# LIC_rack_OV-03.net
KiCad netlist of a schematic drawn in EAGLE
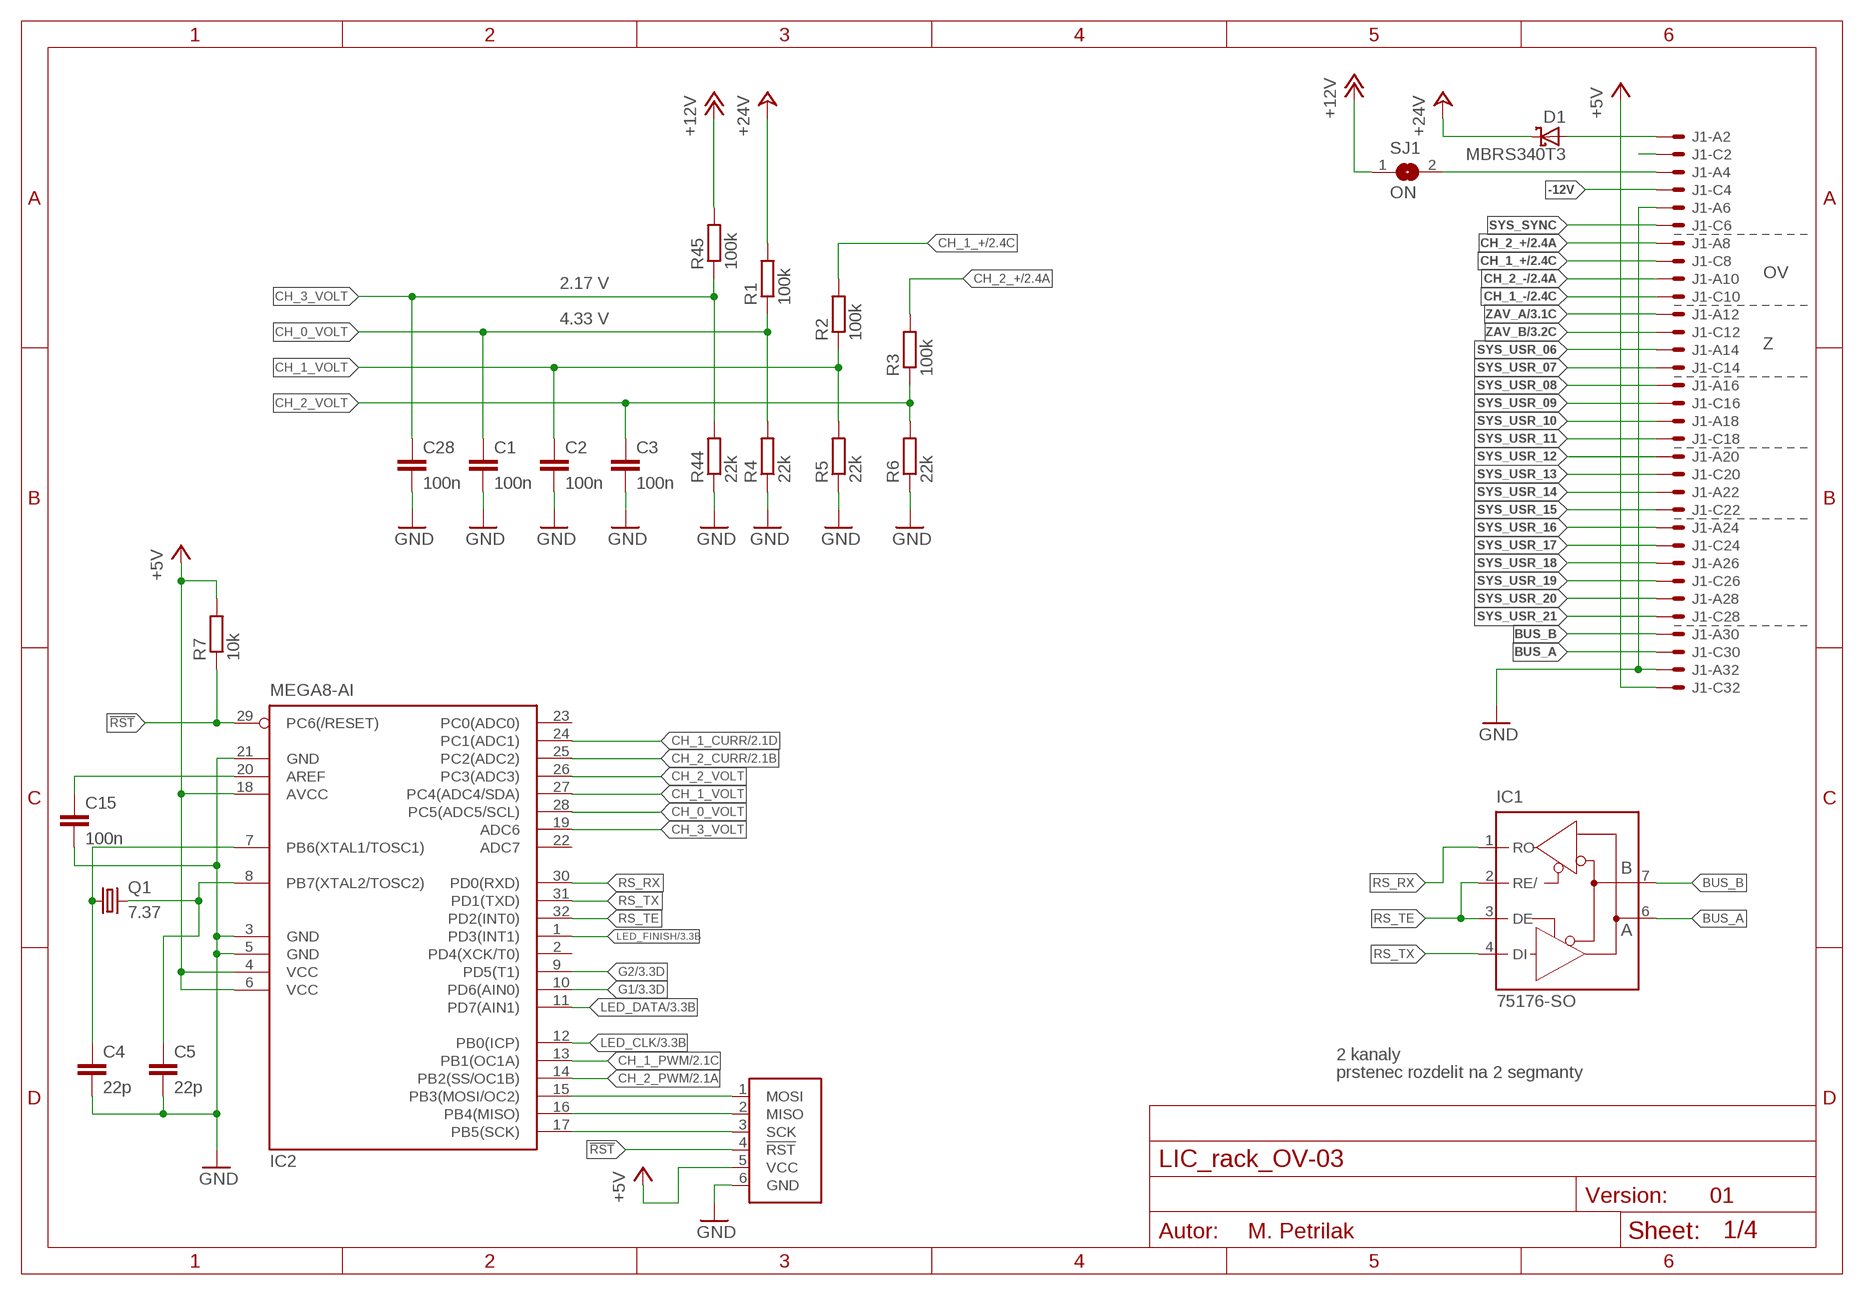
[diagram p0: schematic, sheet 1]
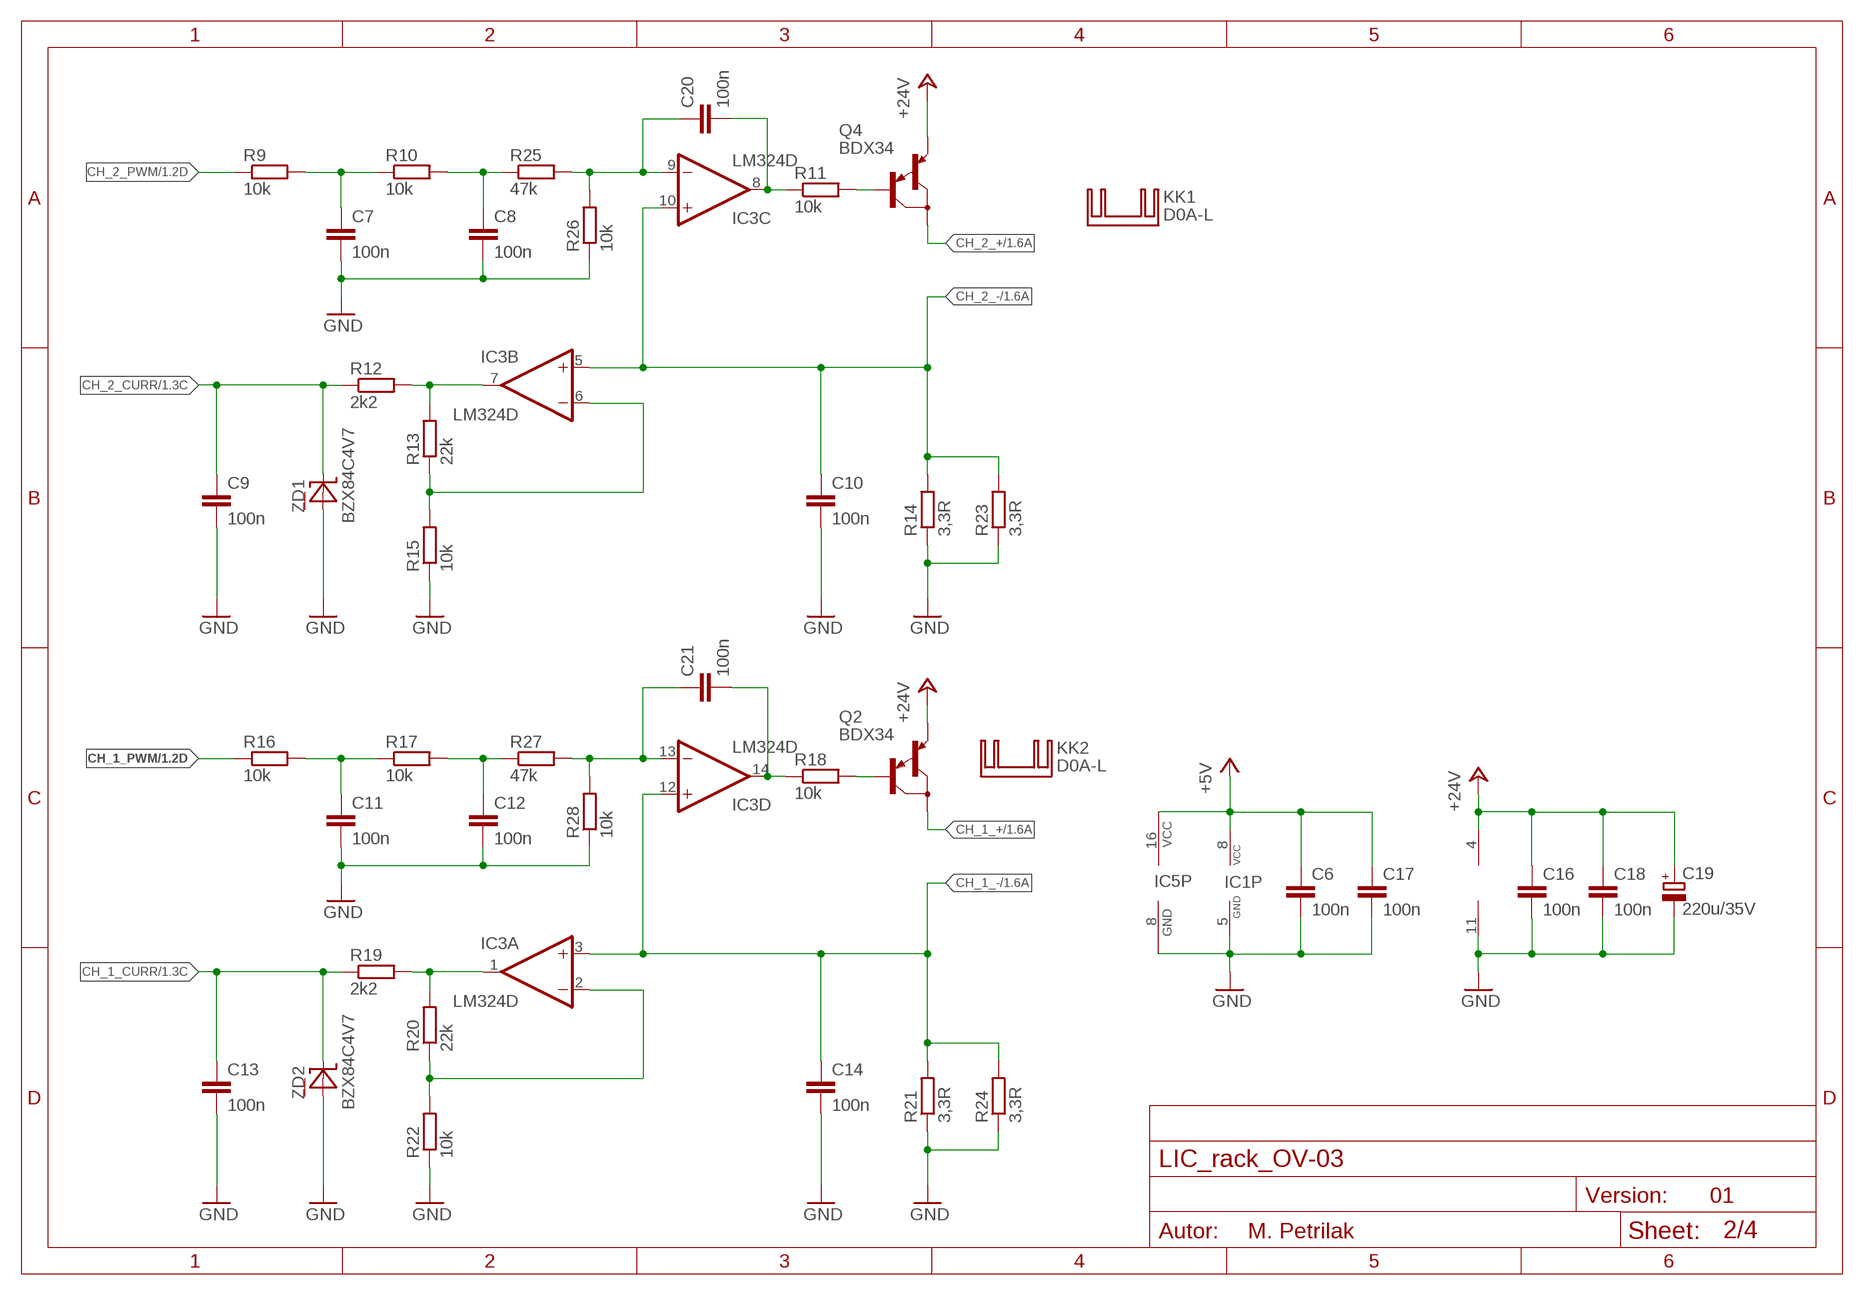
[diagram p1: schematic, sheet 2]
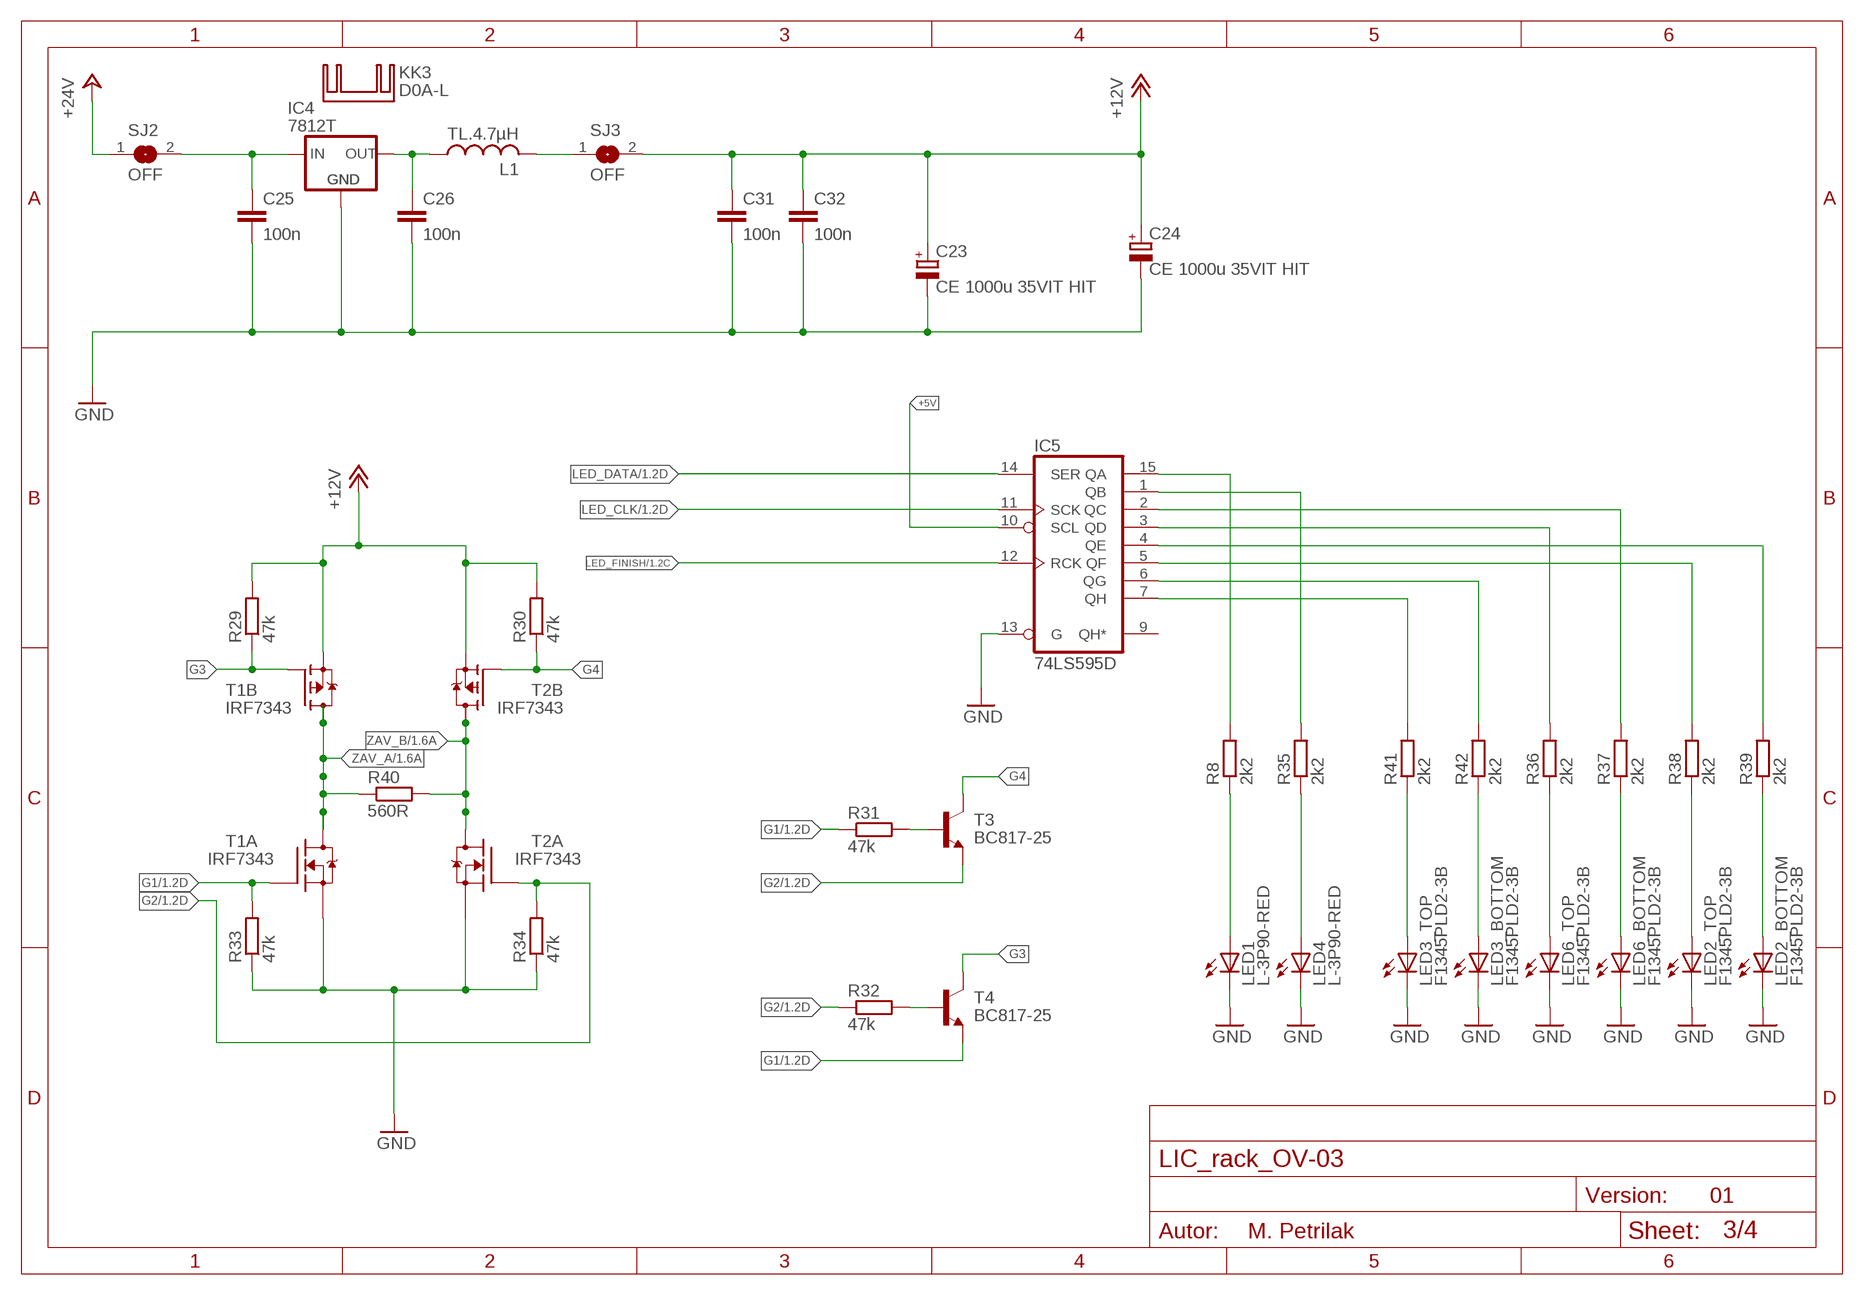
[diagram p2: schematic, sheet 3]

(export (version "E")
  (design (tool "Eeschema 10.0.6"))
  (components
    (comp (ref "C6")
      (value "100n")
      (footprint "eagle-import:C1206")
      (libsource (lib "eagle-import") (part "C-EUC1206"))
    )
    (comp (ref "C7")
      (value "100n")
      (footprint "eagle-import:C1206")
      (libsource (lib "eagle-import") (part "C-EUC1206"))
    )
    (comp (ref "C8")
      (value "100n")
      (footprint "eagle-import:C1206")
      (libsource (lib "eagle-import") (part "C-EUC1206"))
    )
    (comp (ref "C9")
      (value "100n")
      (footprint "eagle-import:C1206")
      (libsource (lib "eagle-import") (part "C-EUC1206"))
    )
    (comp (ref "C10")
      (value "100n")
      (footprint "eagle-import:C1206")
      (libsource (lib "eagle-import") (part "C-EUC1206"))
    )
    (comp (ref "C11")
      (value "100n")
      (footprint "eagle-import:C1206")
      (libsource (lib "eagle-import") (part "C-EUC1206"))
    )
    (comp (ref "C12")
      (value "100n")
      (footprint "eagle-import:C1206")
      (libsource (lib "eagle-import") (part "C-EUC1206"))
    )
    (comp (ref "C13")
      (value "100n")
      (footprint "eagle-import:C1206")
      (libsource (lib "eagle-import") (part "C-EUC1206"))
    )
    (comp (ref "C14")
      (value "100n")
      (footprint "eagle-import:C1206")
      (libsource (lib "eagle-import") (part "C-EUC1206"))
    )
    (comp (ref "C16")
      (value "100n")
      (footprint "eagle-import:C1206")
      (libsource (lib "eagle-import") (part "C-EUC1206"))
    )
    (comp (ref "C17")
      (value "100n")
      (footprint "eagle-import:C1206")
      (libsource (lib "eagle-import") (part "C-EUC1206"))
    )
    (comp (ref "C18")
      (value "100n")
      (footprint "eagle-import:C1206")
      (libsource (lib "eagle-import") (part "C-EUC1206"))
    )
    (comp (ref "C19")
      (value "220u/35V")
      (footprint "eagle-import:E3,5-8LR")
      (libsource (lib "eagle-import") (part "CPOL-EUE3.5-8LR"))
    )
    (comp (ref "C20")
      (value "100n")
      (footprint "eagle-import:C1206")
      (libsource (lib "eagle-import") (part "C-EUC1206"))
    )
    (comp (ref "C21")
      (value "100n")
      (footprint "eagle-import:C1206")
      (libsource (lib "eagle-import") (part "C-EUC1206"))
    )
    (comp (ref "IC1")
      (value "75176-SO")
      (footprint "eagle-import:SO08")
      (libsource (lib "eagle-import") (part "75176-SO"))
    )
    (comp (ref "IC3")
      (value "LM324D")
      (footprint "eagle-import:SO14")
      (libsource (lib "eagle-import") (part "LM324D"))
    )
    (comp (ref "IC5")
      (value "74LS595D")
      (footprint "eagle-import:SO16")
      (libsource (lib "eagle-import") (part "74595DLS"))
    )
    (comp (ref "KK1")
      (value "D0A-L")
      (footprint "eagle-import:D02A-L")
      (libsource (lib "eagle-import") (part "D0A-L"))
    )
    (comp (ref "KK2")
      (value "D0A-L")
      (footprint "eagle-import:D02A-L")
      (libsource (lib "eagle-import") (part "D0A-L"))
    )
    (comp (ref "Q2")
      (value "BDX34")
      (footprint "eagle-import:TO220")
      (libsource (lib "eagle-import") (part "BDX34"))
    )
    (comp (ref "Q4")
      (value "BDX34")
      (footprint "eagle-import:TO220")
      (libsource (lib "eagle-import") (part "BDX34"))
    )
    (comp (ref "R9")
      (value "10k")
      (footprint "eagle-import:R1206")
      (libsource (lib "eagle-import") (part "R-EU_R1206"))
    )
    (comp (ref "R10")
      (value "10k")
      (footprint "eagle-import:R1206")
      (libsource (lib "eagle-import") (part "R-EU_R1206"))
    )
    (comp (ref "R11")
      (value "10k")
      (footprint "eagle-import:R1206")
      (libsource (lib "eagle-import") (part "R-EU_R1206"))
    )
    (comp (ref "R12")
      (value "2k2")
      (footprint "eagle-import:R1206")
      (libsource (lib "eagle-import") (part "R-EU_R1206"))
    )
    (comp (ref "R13")
      (value "22k")
      (footprint "eagle-import:R1206")
      (libsource (lib "eagle-import") (part "R-EU_R1206"))
    )
    (comp (ref "R14")
      (value "3,3R")
      (footprint "eagle-import:0309_12")
      (libsource (lib "eagle-import") (part "R-EU_0309/12"))
    )
    (comp (ref "R15")
      (value "10k")
      (footprint "eagle-import:R1206")
      (libsource (lib "eagle-import") (part "R-EU_R1206"))
    )
    (comp (ref "R16")
      (value "10k")
      (footprint "eagle-import:R1206")
      (libsource (lib "eagle-import") (part "R-EU_R1206"))
    )
    (comp (ref "R17")
      (value "10k")
      (footprint "eagle-import:R1206")
      (libsource (lib "eagle-import") (part "R-EU_R1206"))
    )
    (comp (ref "R18")
      (value "10k")
      (footprint "eagle-import:R1206")
      (libsource (lib "eagle-import") (part "R-EU_R1206"))
    )
    (comp (ref "R19")
      (value "2k2")
      (footprint "eagle-import:R1206")
      (libsource (lib "eagle-import") (part "R-EU_R1206"))
    )
    (comp (ref "R20")
      (value "22k")
      (footprint "eagle-import:R1206")
      (libsource (lib "eagle-import") (part "R-EU_R1206"))
    )
    (comp (ref "R21")
      (value "3,3R")
      (footprint "eagle-import:0309_12")
      (libsource (lib "eagle-import") (part "R-EU_0309/12"))
    )
    (comp (ref "R22")
      (value "10k")
      (footprint "eagle-import:R1206")
      (libsource (lib "eagle-import") (part "R-EU_R1206"))
    )
    (comp (ref "R23")
      (value "3,3R")
      (footprint "eagle-import:R1206")
      (libsource (lib "eagle-import") (part "R-EU_R1206"))
    )
    (comp (ref "R24")
      (value "3,3R")
      (footprint "eagle-import:R1206")
      (libsource (lib "eagle-import") (part "R-EU_R1206"))
    )
    (comp (ref "R25")
      (value "47k")
      (footprint "eagle-import:R1206")
      (libsource (lib "eagle-import") (part "R-EU_R1206"))
    )
    (comp (ref "R26")
      (value "10k")
      (footprint "eagle-import:R1206")
      (libsource (lib "eagle-import") (part "R-EU_R1206"))
    )
    (comp (ref "R27")
      (value "47k")
      (footprint "eagle-import:R1206")
      (libsource (lib "eagle-import") (part "R-EU_R1206"))
    )
    (comp (ref "R28")
      (value "10k")
      (footprint "eagle-import:R1206")
      (libsource (lib "eagle-import") (part "R-EU_R1206"))
    )
    (comp (ref "ZD1")
      (value "BZX84C4V7")
      (footprint "eagle-import:SOT23")
      (libsource (lib "eagle-import") (part "BZX84C4V7"))
    )
    (comp (ref "ZD2")
      (value "BZX84C4V7")
      (footprint "eagle-import:SOT23")
      (libsource (lib "eagle-import") (part "BZX84C4V7"))
    )
    (comp (ref "C1")
      (value "100n")
      (footprint "eagle-import:C1206")
      (libsource (lib "eagle-import") (part "C-EUC1206"))
    )
    (comp (ref "C2")
      (value "100n")
      (footprint "eagle-import:C1206")
      (libsource (lib "eagle-import") (part "C-EUC1206"))
    )
    (comp (ref "C3")
      (value "100n")
      (footprint "eagle-import:C1206")
      (libsource (lib "eagle-import") (part "C-EUC1206"))
    )
    (comp (ref "C4")
      (value "22p")
      (footprint "eagle-import:C0805")
      (libsource (lib "eagle-import") (part "C-EUC0805"))
    )
    (comp (ref "C5")
      (value "22p")
      (footprint "eagle-import:C0805")
      (libsource (lib "eagle-import") (part "C-EUC0805"))
    )
    (comp (ref "C15")
      (value "100n")
      (footprint "eagle-import:C1206")
      (libsource (lib "eagle-import") (part "C-EUC1206"))
    )
    (comp (ref "C28")
      (value "100n")
      (footprint "eagle-import:C1206")
      (libsource (lib "eagle-import") (part "C-EUC1206"))
    )
    (comp (ref "D1")
      (value "MBRS340T3")
      (footprint "eagle-import:SMC")
      (libsource (lib "eagle-import") (part "MBRS340T3"))
    )
    (comp (ref "IC2")
      (value "MEGA8-AI")
      (footprint "eagle-import:TQFP32-08")
      (libsource (lib "eagle-import") (part "MEGA8-AI"))
    )
    (comp (ref "J1")
      (value "VG32SP")
      (footprint "eagle-import:VG32P")
      (libsource (lib "eagle-import") (part "VG32SP"))
    )
    (comp (ref "Q1")
      (value "7.37")
      (footprint "eagle-import:HC49U70")
      (libsource (lib "eagle-import") (part "XTAL"))
    )
    (comp (ref "R1")
      (value "100k")
      (footprint "eagle-import:R1206")
      (libsource (lib "eagle-import") (part "R-EU_R1206"))
    )
    (comp (ref "R2")
      (value "100k")
      (footprint "eagle-import:R1206")
      (libsource (lib "eagle-import") (part "R-EU_R1206"))
    )
    (comp (ref "R3")
      (value "100k")
      (footprint "eagle-import:R1206")
      (libsource (lib "eagle-import") (part "R-EU_R1206"))
    )
    (comp (ref "R4")
      (value "22k")
      (footprint "eagle-import:R1206")
      (libsource (lib "eagle-import") (part "R-EU_R1206"))
    )
    (comp (ref "R5")
      (value "22k")
      (footprint "eagle-import:R1206")
      (libsource (lib "eagle-import") (part "R-EU_R1206"))
    )
    (comp (ref "R6")
      (value "22k")
      (footprint "eagle-import:R1206")
      (libsource (lib "eagle-import") (part "R-EU_R1206"))
    )
    (comp (ref "R7")
      (value "10k")
      (footprint "eagle-import:R1206")
      (libsource (lib "eagle-import") (part "R-EU_R1206"))
    )
    (comp (ref "R44")
      (value "22k")
      (footprint "eagle-import:R1206")
      (libsource (lib "eagle-import") (part "R-EU_R1206"))
    )
    (comp (ref "R45")
      (value "100k")
      (footprint "eagle-import:R1206")
      (libsource (lib "eagle-import") (part "R-EU_R1206"))
    )
    (comp (ref "SJ1")
      (value "ON")
      (footprint "eagle-import:SJ-D")
      (libsource (lib "eagle-import") (part "SJ-DEFAULT"))
    )
    (comp (ref "U1")
      (value "ATPROG-V")
      (footprint "eagle-import:6410-06")
      (libsource (lib "eagle-import") (part "ATPROG-V"))
    )
    (comp (ref "C23")
      (value "CE 1000u 35VIT HIT")
      (footprint "eagle-import:E5-13X26-LR")
      (libsource (lib "eagle-import") (part "CPOL-EUE5-13X26-LR"))
    )
    (comp (ref "C24")
      (value "CE 1000u 35VIT HIT")
      (footprint "eagle-import:E5-13X26-LR")
      (libsource (lib "eagle-import") (part "CPOL-EUE5-13X26-LR"))
    )
    (comp (ref "C25")
      (value "100n")
      (footprint "eagle-import:C1206")
      (libsource (lib "eagle-import") (part "C-EUC1206"))
    )
    (comp (ref "C26")
      (value "100n")
      (footprint "eagle-import:C1206")
      (libsource (lib "eagle-import") (part "C-EUC1206"))
    )
    (comp (ref "C31")
      (value "100n")
      (footprint "eagle-import:C1206")
      (libsource (lib "eagle-import") (part "C-EUC1206"))
    )
    (comp (ref "C32")
      (value "100n")
      (footprint "eagle-import:C1206")
      (libsource (lib "eagle-import") (part "C-EUC1206"))
    )
    (comp (ref "IC4")
      (value "7812T")
      (footprint "eagle-import:TO220H")
      (libsource (lib "eagle-import") (part "78T12"))
    )
    (comp (ref "KK3")
      (value "D0A-L")
      (footprint "eagle-import:D02A-L")
      (libsource (lib "eagle-import") (part "D0A-L"))
    )
    (comp (ref "L1")
      (value "TL.4.7µH")
      (footprint "eagle-import:0207_12")
      (libsource (lib "eagle-import") (part "L-EU0207/12"))
    )
    (comp (ref "LED1")
      (value "L-3P90-RED")
      (footprint "eagle-import:L-3P90")
      (libsource (lib "eagle-import") (part "L-3P90-RED"))
    )
    (comp (ref "LED2")
      (value "F1345PLD2-3B")
      (footprint "eagle-import:F1345PLD2-3B")
      (libsource (lib "eagle-import") (part "F1345PLD2-3B"))
    )
    (comp (ref "LED3")
      (value "F1345PLD2-3B")
      (footprint "eagle-import:F1345PLD2-3B")
      (libsource (lib "eagle-import") (part "F1345PLD2-3B"))
    )
    (comp (ref "LED4")
      (value "L-3P90-RED")
      (footprint "eagle-import:L-3P90")
      (libsource (lib "eagle-import") (part "L-3P90-RED"))
    )
    (comp (ref "LED6")
      (value "F1345PLD2-3B")
      (footprint "eagle-import:F1345PLD2-3B")
      (libsource (lib "eagle-import") (part "F1345PLD2-3B"))
    )
    (comp (ref "R8")
      (value "2k2")
      (footprint "eagle-import:R1206")
      (libsource (lib "eagle-import") (part "R-EU_R1206"))
    )
    (comp (ref "R29")
      (value "47k")
      (footprint "eagle-import:R1206")
      (libsource (lib "eagle-import") (part "R-EU_R1206"))
    )
    (comp (ref "R30")
      (value "47k")
      (footprint "eagle-import:R1206")
      (libsource (lib "eagle-import") (part "R-EU_R1206"))
    )
    (comp (ref "R31")
      (value "47k")
      (footprint "eagle-import:R1206")
      (libsource (lib "eagle-import") (part "R-EU_R1206"))
    )
    (comp (ref "R32")
      (value "47k")
      (footprint "eagle-import:R1206")
      (libsource (lib "eagle-import") (part "R-EU_R1206"))
    )
    (comp (ref "R33")
      (value "47k")
      (footprint "eagle-import:R1206")
      (libsource (lib "eagle-import") (part "R-EU_R1206"))
    )
    (comp (ref "R34")
      (value "47k")
      (footprint "eagle-import:R1206")
      (libsource (lib "eagle-import") (part "R-EU_R1206"))
    )
    (comp (ref "R35")
      (value "2k2")
      (footprint "eagle-import:R1206")
      (libsource (lib "eagle-import") (part "R-EU_R1206"))
    )
    (comp (ref "R36")
      (value "2k2")
      (footprint "eagle-import:R1206")
      (libsource (lib "eagle-import") (part "R-EU_R1206"))
    )
    (comp (ref "R37")
      (value "2k2")
      (footprint "eagle-import:R1206")
      (libsource (lib "eagle-import") (part "R-EU_R1206"))
    )
    (comp (ref "R38")
      (value "2k2")
      (footprint "eagle-import:R1206")
      (libsource (lib "eagle-import") (part "R-EU_R1206"))
    )
    (comp (ref "R39")
      (value "2k2")
      (footprint "eagle-import:R1206")
      (libsource (lib "eagle-import") (part "R-EU_R1206"))
    )
    (comp (ref "R40")
      (value "560R")
      (footprint "eagle-import:R1206")
      (libsource (lib "eagle-import") (part "R-EU_R1206"))
    )
    (comp (ref "R41")
      (value "2k2")
      (footprint "eagle-import:R1206")
      (libsource (lib "eagle-import") (part "R-EU_R1206"))
    )
    (comp (ref "R42")
      (value "2k2")
      (footprint "eagle-import:R1206")
      (libsource (lib "eagle-import") (part "R-EU_R1206"))
    )
    (comp (ref "SJ2")
      (value "OFF")
      (footprint "eagle-import:SJ")
      (libsource (lib "eagle-import") (part "SJ"))
    )
    (comp (ref "SJ3")
      (value "OFF")
      (footprint "eagle-import:SJ")
      (libsource (lib "eagle-import") (part "SJ"))
    )
    (comp (ref "T1")
      (value "IRF7343")
      (footprint "eagle-import:SO-8")
      (libsource (lib "eagle-import") (part "IRF7343"))
    )
    (comp (ref "T2")
      (value "IRF7343")
      (footprint "eagle-import:SO-8")
      (libsource (lib "eagle-import") (part "IRF7343"))
    )
    (comp (ref "T3")
      (value "BC817-25")
      (footprint "eagle-import:SOT23-BEC")
      (libsource (lib "eagle-import") (part "-NPN-SOT23-BECBC817-25"))
    )
    (comp (ref "T4")
      (value "BC817-25")
      (footprint "eagle-import:SOT23-BEC")
      (libsource (lib "eagle-import") (part "-NPN-SOT23-BECBC817-25"))
    )
  )
  (nets
    (net (code "1") (name "+5V") (class "Default")
      (node (ref "C17") (pin "1") (pinfunction "1_1") (pintype "passive"))
      (node (ref "C6") (pin "1") (pinfunction "1_1") (pintype "passive"))
      (node (ref "IC1") (pin "8") (pinfunction "VCC_8") (pintype "power_in"))
      (node (ref "IC2") (pin "18") (pinfunction "AVCC_18") (pintype "power_in"))
      (node (ref "IC2") (pin "4") (pinfunction "VCC_4") (pintype "power_in"))
      (node (ref "IC2") (pin "6") (pinfunction "VCC_6") (pintype "power_in"))
      (node (ref "IC5") (pin "10") (pinfunction "SCL_10") (pintype "input"))
      (node (ref "IC5") (pin "16") (pinfunction "VCC_16") (pintype "power_in"))
      (node (ref "J1") (pin "C32") (pinfunction "MSV_C32") (pintype "passive"))
      (node (ref "R7") (pin "2") (pinfunction "2_2") (pintype "passive"))
      (node (ref "U1") (pin "5") (pinfunction "VCC_5") (pintype "power_in"))
    )
    (net (code "2") (name "+12V") (class "Default")
      (node (ref "C23") (pin "+") (pinfunction "+_+") (pintype "passive"))
      (node (ref "C24") (pin "+") (pinfunction "+_+") (pintype "passive"))
      (node (ref "C31") (pin "1") (pinfunction "1_1") (pintype "passive"))
      (node (ref "C32") (pin "1") (pinfunction "1_1") (pintype "passive"))
      (node (ref "R29") (pin "2") (pinfunction "2_2") (pintype "passive"))
      (node (ref "R30") (pin "2") (pinfunction "2_2") (pintype "passive"))
      (node (ref "R45") (pin "2") (pinfunction "2_2") (pintype "passive"))
      (node (ref "SJ1") (pin "1") (pinfunction "1_1") (pintype "passive"))
      (node (ref "SJ3") (pin "2") (pinfunction "2_2") (pintype "passive"))
      (node (ref "T1") (pin "3") (pinfunction "S_3") (pintype "passive"))
      (node (ref "T2") (pin "3") (pinfunction "S_3") (pintype "passive"))
    )
    (net (code "3") (name "+24V") (class "Default")
      (node (ref "C16") (pin "1") (pinfunction "1_1") (pintype "passive"))
      (node (ref "C18") (pin "1") (pinfunction "1_1") (pintype "passive"))
      (node (ref "C19") (pin "+") (pinfunction "+_+") (pintype "passive"))
      (node (ref "D1") (pin "C") (pinfunction "C_C") (pintype "passive"))
      (node (ref "IC3") (pin "4") (pinfunction "V+_4") (pintype "power_in"))
      (node (ref "Q2") (pin "3") (pinfunction "E_3") (pintype "passive"))
      (node (ref "Q4") (pin "3") (pinfunction "E_3") (pintype "passive"))
      (node (ref "R1") (pin "2") (pinfunction "2_2") (pintype "passive"))
      (node (ref "SJ2") (pin "1") (pinfunction "1_1") (pintype "passive"))
    )
    (net (code "4") (name "-12V") (class "Default")
      (node (ref "J1") (pin "C4") (pinfunction "MS_C4") (pintype "passive"))
    )
    (net (code "5") (name "BUS_A") (class "Default")
      (node (ref "IC1") (pin "6") (pinfunction "A_6") (pintype "passive"))
      (node (ref "J1") (pin "C30") (pinfunction "MS_C30") (pintype "passive"))
    )
    (net (code "6") (name "BUS_B") (class "Default")
      (node (ref "IC1") (pin "7") (pinfunction "B_7") (pintype "passive"))
      (node (ref "J1") (pin "A30") (pinfunction "MS_A30") (pintype "passive"))
    )
    (net (code "7") (name "CH_0_VOLT") (class "Default")
      (node (ref "C1") (pin "1") (pinfunction "1_1") (pintype "passive"))
      (node (ref "IC2") (pin "28") (pinfunction "PC5(ADC5/SCL)_28") (pintype "bidirectional"))
      (node (ref "R1") (pin "1") (pinfunction "1_1") (pintype "passive"))
      (node (ref "R4") (pin "2") (pinfunction "2_2") (pintype "passive"))
    )
    (net (code "8") (name "CH_1_+") (class "Default")
      (node (ref "J1") (pin "C8") (pinfunction "MS_C8") (pintype "passive"))
      (node (ref "Q2") (pin "2") (pinfunction "C_2") (pintype "passive"))
      (node (ref "R2") (pin "2") (pinfunction "2_2") (pintype "passive"))
    )
    (net (code "9") (name "CH_1_-") (class "Default")
      (node (ref "C14") (pin "1") (pinfunction "1_1") (pintype "passive"))
      (node (ref "IC3") (pin "12") (pinfunction "+IN_12") (pintype "input"))
      (node (ref "IC3") (pin "3") (pinfunction "+IN_3") (pintype "input"))
      (node (ref "J1") (pin "C10") (pinfunction "MS_C10") (pintype "passive"))
      (node (ref "R21") (pin "2") (pinfunction "2_2") (pintype "passive"))
      (node (ref "R24") (pin "2") (pinfunction "2_2") (pintype "passive"))
    )
    (net (code "10") (name "CH_1_CURR") (class "Default")
      (node (ref "C13") (pin "1") (pinfunction "1_1") (pintype "passive"))
      (node (ref "IC2") (pin "24") (pinfunction "PC1(ADC1)_24") (pintype "bidirectional"))
      (node (ref "R19") (pin "1") (pinfunction "1_1") (pintype "passive"))
      (node (ref "ZD2") (pin "3") (pinfunction "C_3") (pintype "passive"))
    )
    (net (code "11") (name "CH_1_PWM") (class "Default")
      (node (ref "IC2") (pin "13") (pinfunction "PB1(OC1A)_13") (pintype "bidirectional"))
      (node (ref "R16") (pin "1") (pinfunction "1_1") (pintype "passive"))
    )
    (net (code "12") (name "CH_1_VOLT") (class "Default")
      (node (ref "C2") (pin "1") (pinfunction "1_1") (pintype "passive"))
      (node (ref "IC2") (pin "27") (pinfunction "PC4(ADC4/SDA)_27") (pintype "bidirectional"))
      (node (ref "R2") (pin "1") (pinfunction "1_1") (pintype "passive"))
      (node (ref "R5") (pin "2") (pinfunction "2_2") (pintype "passive"))
    )
    (net (code "13") (name "CH_2_+") (class "Default")
      (node (ref "J1") (pin "A8") (pinfunction "MS_A8") (pintype "passive"))
      (node (ref "Q4") (pin "2") (pinfunction "C_2") (pintype "passive"))
      (node (ref "R3") (pin "2") (pinfunction "2_2") (pintype "passive"))
    )
    (net (code "14") (name "CH_2_-") (class "Default")
      (node (ref "C10") (pin "1") (pinfunction "1_1") (pintype "passive"))
      (node (ref "IC3") (pin "10") (pinfunction "+IN_10") (pintype "input"))
      (node (ref "IC3") (pin "5") (pinfunction "+IN_5") (pintype "input"))
      (node (ref "J1") (pin "A10") (pinfunction "MS_A10") (pintype "passive"))
      (node (ref "R14") (pin "2") (pinfunction "2_2") (pintype "passive"))
      (node (ref "R23") (pin "2") (pinfunction "2_2") (pintype "passive"))
    )
    (net (code "15") (name "CH_2_CURR") (class "Default")
      (node (ref "C9") (pin "1") (pinfunction "1_1") (pintype "passive"))
      (node (ref "IC2") (pin "25") (pinfunction "PC2(ADC2)_25") (pintype "bidirectional"))
      (node (ref "R12") (pin "1") (pinfunction "1_1") (pintype "passive"))
      (node (ref "ZD1") (pin "3") (pinfunction "C_3") (pintype "passive"))
    )
    (net (code "16") (name "CH_2_PWM") (class "Default")
      (node (ref "IC2") (pin "14") (pinfunction "PB2(SS/OC1B)_14") (pintype "bidirectional"))
      (node (ref "R9") (pin "1") (pinfunction "1_1") (pintype "passive"))
    )
    (net (code "17") (name "CH_2_VOLT") (class "Default")
      (node (ref "C3") (pin "1") (pinfunction "1_1") (pintype "passive"))
      (node (ref "IC2") (pin "26") (pinfunction "PC3(ADC3)_26") (pintype "bidirectional"))
      (node (ref "R3") (pin "1") (pinfunction "1_1") (pintype "passive"))
      (node (ref "R6") (pin "2") (pinfunction "2_2") (pintype "passive"))
    )
    (net (code "18") (name "CH_3_VOLT") (class "Default")
      (node (ref "C28") (pin "1") (pinfunction "1_1") (pintype "passive"))
      (node (ref "IC2") (pin "19") (pinfunction "ADC6_19") (pintype "bidirectional"))
      (node (ref "R44") (pin "2") (pinfunction "2_2") (pintype "passive"))
      (node (ref "R45") (pin "1") (pinfunction "1_1") (pintype "passive"))
    )
    (net (code "19") (name "G1") (class "Default")
      (node (ref "IC2") (pin "10") (pinfunction "PD6(AIN0)_10") (pintype "bidirectional"))
      (node (ref "R31") (pin "1") (pinfunction "1_1") (pintype "passive"))
      (node (ref "R33") (pin "2") (pinfunction "2_2") (pintype "passive"))
      (node (ref "T1") (pin "2") (pinfunction "G_2") (pintype "passive"))
      (node (ref "T4") (pin "E") (pinfunction "E_E") (pintype "passive"))
    )
    (net (code "20") (name "G2") (class "Default")
      (node (ref "IC2") (pin "9") (pinfunction "PD5(T1)_9") (pintype "bidirectional"))
      (node (ref "R32") (pin "1") (pinfunction "1_1") (pintype "passive"))
      (node (ref "R34") (pin "2") (pinfunction "2_2") (pintype "passive"))
      (node (ref "T2") (pin "2") (pinfunction "G_2") (pintype "passive"))
      (node (ref "T3") (pin "E") (pinfunction "E_E") (pintype "passive"))
    )
    (net (code "21") (name "G3") (class "Default")
      (node (ref "R29") (pin "1") (pinfunction "1_1") (pintype "passive"))
      (node (ref "T1") (pin "4") (pinfunction "G_4") (pintype "passive"))
      (node (ref "T4") (pin "C") (pinfunction "C_C") (pintype "passive"))
    )
    (net (code "22") (name "G4") (class "Default")
      (node (ref "R30") (pin "1") (pinfunction "1_1") (pintype "passive"))
      (node (ref "T2") (pin "4") (pinfunction "G_4") (pintype "passive"))
      (node (ref "T3") (pin "C") (pinfunction "C_C") (pintype "passive"))
    )
    (net (code "23") (name "GND") (class "Default")
      (node (ref "C1") (pin "2") (pinfunction "2_2") (pintype "passive"))
      (node (ref "C10") (pin "2") (pinfunction "2_2") (pintype "passive"))
      (node (ref "C11") (pin "2") (pinfunction "2_2") (pintype "passive"))
      (node (ref "C12") (pin "2") (pinfunction "2_2") (pintype "passive"))
      (node (ref "C13") (pin "2") (pinfunction "2_2") (pintype "passive"))
      (node (ref "C14") (pin "2") (pinfunction "2_2") (pintype "passive"))
      (node (ref "C15") (pin "2") (pinfunction "2_2") (pintype "passive"))
      (node (ref "C16") (pin "2") (pinfunction "2_2") (pintype "passive"))
      (node (ref "C17") (pin "2") (pinfunction "2_2") (pintype "passive"))
      (node (ref "C18") (pin "2") (pinfunction "2_2") (pintype "passive"))
      (node (ref "C19") (pin "-") (pinfunction "-_-") (pintype "passive"))
      (node (ref "C2") (pin "2") (pinfunction "2_2") (pintype "passive"))
      (node (ref "C23") (pin "-") (pinfunction "-_-") (pintype "passive"))
      (node (ref "C24") (pin "-") (pinfunction "-_-") (pintype "passive"))
      (node (ref "C25") (pin "2") (pinfunction "2_2") (pintype "passive"))
      (node (ref "C26") (pin "2") (pinfunction "2_2") (pintype "passive"))
      (node (ref "C28") (pin "2") (pinfunction "2_2") (pintype "passive"))
      (node (ref "C3") (pin "2") (pinfunction "2_2") (pintype "passive"))
      (node (ref "C31") (pin "2") (pinfunction "2_2") (pintype "passive"))
      (node (ref "C32") (pin "2") (pinfunction "2_2") (pintype "passive"))
      (node (ref "C4") (pin "2") (pinfunction "2_2") (pintype "passive"))
      (node (ref "C5") (pin "2") (pinfunction "2_2") (pintype "passive"))
      (node (ref "C6") (pin "2") (pinfunction "2_2") (pintype "passive"))
      (node (ref "C7") (pin "2") (pinfunction "2_2") (pintype "passive"))
      (node (ref "C8") (pin "2") (pinfunction "2_2") (pintype "passive"))
      (node (ref "C9") (pin "2") (pinfunction "2_2") (pintype "passive"))
      (node (ref "IC1") (pin "5") (pinfunction "GND_5") (pintype "power_in"))
      (node (ref "IC2") (pin "21") (pinfunction "GND_21") (pintype "power_in"))
      (node (ref "IC2") (pin "3") (pinfunction "GND_3") (pintype "power_in"))
      (node (ref "IC2") (pin "5") (pinfunction "GND_5") (pintype "power_in"))
      (node (ref "IC3") (pin "11") (pinfunction "V-_11") (pintype "power_in"))
      (node (ref "IC4") (pin "2") (pinfunction "GND_2") (pintype "passive"))
      (node (ref "IC5") (pin "13") (pinfunction "G_13") (pintype "input"))
      (node (ref "IC5") (pin "8") (pinfunction "GND_8") (pintype "power_in"))
      (node (ref "J1") (pin "A32") (pinfunction "MS_A32") (pintype "passive"))
      (node (ref "J1") (pin "A6") (pinfunction "MS_A6") (pintype "passive"))
      (node (ref "LED1") (pin "K") (pinfunction "C_K") (pintype "passive"))
      (node (ref "LED2") (pin "1K") (pinfunction "C_1K") (pintype "passive"))
      (node (ref "LED2") (pin "2K") (pinfunction "C_2K") (pintype "passive"))
      (node (ref "LED3") (pin "1K") (pinfunction "C_1K") (pintype "passive"))
      (node (ref "LED3") (pin "2K") (pinfunction "C_2K") (pintype "passive"))
      (node (ref "LED4") (pin "K") (pinfunction "C_K") (pintype "passive"))
      (node (ref "LED6") (pin "1K") (pinfunction "C_1K") (pintype "passive"))
      (node (ref "LED6") (pin "2K") (pinfunction "C_2K") (pintype "passive"))
      (node (ref "R14") (pin "1") (pinfunction "1_1") (pintype "passive"))
      (node (ref "R15") (pin "1") (pinfunction "1_1") (pintype "passive"))
      (node (ref "R21") (pin "1") (pinfunction "1_1") (pintype "passive"))
      (node (ref "R22") (pin "1") (pinfunction "1_1") (pintype "passive"))
      (node (ref "R23") (pin "1") (pinfunction "1_1") (pintype "passive"))
      (node (ref "R24") (pin "1") (pinfunction "1_1") (pintype "passive"))
      (node (ref "R26") (pin "1") (pinfunction "1_1") (pintype "passive"))
      (node (ref "R28") (pin "1") (pinfunction "1_1") (pintype "passive"))
      (node (ref "R33") (pin "1") (pinfunction "1_1") (pintype "passive"))
      (node (ref "R34") (pin "1") (pinfunction "1_1") (pintype "passive"))
      (node (ref "R4") (pin "1") (pinfunction "1_1") (pintype "passive"))
      (node (ref "R44") (pin "1") (pinfunction "1_1") (pintype "passive"))
      (node (ref "R5") (pin "1") (pinfunction "1_1") (pintype "passive"))
      (node (ref "R6") (pin "1") (pinfunction "1_1") (pintype "passive"))
      (node (ref "T1") (pin "1") (pinfunction "S_1") (pintype "passive"))
      (node (ref "T2") (pin "1") (pinfunction "S_1") (pintype "passive"))
      (node (ref "U1") (pin "6") (pinfunction "GND_6") (pintype "power_in"))
      (node (ref "ZD1") (pin "1") (pinfunction "A_1") (pintype "passive"))
      (node (ref "ZD2") (pin "1") (pinfunction "A_1") (pintype "passive"))
    )
    (net (code "24") (name "LED_CLK") (class "Default")
      (node (ref "IC2") (pin "12") (pinfunction "PB0(ICP)_12") (pintype "bidirectional"))
      (node (ref "IC5") (pin "11") (pinfunction "SCK_11") (pintype "input"))
    )
    (net (code "25") (name "LED_DATA") (class "Default")
      (node (ref "IC2") (pin "11") (pinfunction "PD7(AIN1)_11") (pintype "bidirectional"))
      (node (ref "IC5") (pin "14") (pinfunction "SER_14") (pintype "input"))
    )
    (net (code "26") (name "LED_FINISH") (class "Default")
      (node (ref "IC2") (pin "1") (pinfunction "PD3(INT1)_1") (pintype "bidirectional"))
      (node (ref "IC5") (pin "12") (pinfunction "RCK_12") (pintype "input"))
    )
    (net (code "27") (name "Net-(C7-Pad1)") (class "Default")
      (node (ref "C7") (pin "1") (pinfunction "1_1") (pintype "passive"))
      (node (ref "R10") (pin "1") (pinfunction "1_1") (pintype "passive"))
      (node (ref "R9") (pin "2") (pinfunction "2_2") (pintype "passive"))
    )
    (net (code "28") (name "Net-(C8-Pad1)") (class "Default")
      (node (ref "C8") (pin "1") (pinfunction "1_1") (pintype "passive"))
      (node (ref "R10") (pin "2") (pinfunction "2_2") (pintype "passive"))
      (node (ref "R25") (pin "1") (pinfunction "1_1") (pintype "passive"))
    )
    (net (code "29") (name "Net-(C11-Pad1)") (class "Default")
      (node (ref "C11") (pin "1") (pinfunction "1_1") (pintype "passive"))
      (node (ref "R16") (pin "2") (pinfunction "2_2") (pintype "passive"))
      (node (ref "R17") (pin "1") (pinfunction "1_1") (pintype "passive"))
    )
    (net (code "30") (name "Net-(C12-Pad1)") (class "Default")
      (node (ref "C12") (pin "1") (pinfunction "1_1") (pintype "passive"))
      (node (ref "R17") (pin "2") (pinfunction "2_2") (pintype "passive"))
      (node (ref "R27") (pin "1") (pinfunction "1_1") (pintype "passive"))
    )
    (net (code "31") (name "Net-(IC2-AREF)") (class "Default")
      (node (ref "C15") (pin "1") (pinfunction "1_1") (pintype "passive"))
      (node (ref "IC2") (pin "20") (pinfunction "AREF_20") (pintype "passive"))
    )
    (net (code "32") (name "Net-(IC2-PB3(MOSI{slash}OC2))") (class "Default")
      (node (ref "IC2") (pin "15") (pinfunction "PB3(MOSI/OC2)_15") (pintype "bidirectional"))
      (node (ref "U1") (pin "1") (pinfunction "MOSI_1") (pintype "output"))
    )
    (net (code "33") (name "Net-(IC2-PB4(MISO))") (class "Default")
      (node (ref "IC2") (pin "16") (pinfunction "PB4(MISO)_16") (pintype "bidirectional"))
      (node (ref "U1") (pin "2") (pinfunction "MISO_2") (pintype "input"))
    )
    (net (code "34") (name "Net-(IC2-PB5(SCK))") (class "Default")
      (node (ref "IC2") (pin "17") (pinfunction "PB5(SCK)_17") (pintype "bidirectional"))
      (node (ref "U1") (pin "3") (pinfunction "SCK_3") (pintype "input"))
    )
    (net (code "35") (name "Net-(IC2-PB6(XTAL1{slash}TOSC1))") (class "Default")
      (node (ref "C4") (pin "1") (pinfunction "1_1") (pintype "passive"))
      (node (ref "IC2") (pin "7") (pinfunction "PB6(XTAL1/TOSC1)_7") (pintype "bidirectional"))
      (node (ref "Q1") (pin "1") (pinfunction "1_1") (pintype "passive"))
    )
    (net (code "36") (name "Net-(IC2-PB7(XTAL2{slash}TOSC2))") (class "Default")
      (node (ref "C5") (pin "1") (pinfunction "1_1") (pintype "passive"))
      (node (ref "IC2") (pin "8") (pinfunction "PB7(XTAL2/TOSC2)_8") (pintype "bidirectional"))
      (node (ref "Q1") (pin "2") (pinfunction "2_2") (pintype "passive"))
    )
    (net (code "37") (name "Net-(IC3A--IN)") (class "Default")
      (node (ref "IC3") (pin "2") (pinfunction "-IN_2") (pintype "input"))
      (node (ref "R20") (pin "1") (pinfunction "1_1") (pintype "passive"))
      (node (ref "R22") (pin "2") (pinfunction "2_2") (pintype "passive"))
    )
    (net (code "38") (name "Net-(IC3A-OUT)") (class "Default")
      (node (ref "IC3") (pin "1") (pinfunction "OUT_1") (pintype "output"))
      (node (ref "R19") (pin "2") (pinfunction "2_2") (pintype "passive"))
      (node (ref "R20") (pin "2") (pinfunction "2_2") (pintype "passive"))
    )
    (net (code "39") (name "Net-(IC3B--IN)") (class "Default")
      (node (ref "IC3") (pin "6") (pinfunction "-IN_6") (pintype "input"))
      (node (ref "R13") (pin "1") (pinfunction "1_1") (pintype "passive"))
      (node (ref "R15") (pin "2") (pinfunction "2_2") (pintype "passive"))
    )
    (net (code "40") (name "Net-(IC3B-OUT)") (class "Default")
      (node (ref "IC3") (pin "7") (pinfunction "OUT_7") (pintype "output"))
      (node (ref "R12") (pin "2") (pinfunction "2_2") (pintype "passive"))
      (node (ref "R13") (pin "2") (pinfunction "2_2") (pintype "passive"))
    )
    (net (code "41") (name "Net-(IC3C--IN)") (class "Default")
      (node (ref "C20") (pin "1") (pinfunction "1_1") (pintype "passive"))
      (node (ref "IC3") (pin "9") (pinfunction "-IN_9") (pintype "input"))
      (node (ref "R25") (pin "2") (pinfunction "2_2") (pintype "passive"))
      (node (ref "R26") (pin "2") (pinfunction "2_2") (pintype "passive"))
    )
    (net (code "42") (name "Net-(IC3C-OUT)") (class "Default")
      (node (ref "C20") (pin "2") (pinfunction "2_2") (pintype "passive"))
      (node (ref "IC3") (pin "8") (pinfunction "OUT_8") (pintype "output"))
      (node (ref "R11") (pin "1") (pinfunction "1_1") (pintype "passive"))
    )
    (net (code "43") (name "Net-(IC3D--IN)") (class "Default")
      (node (ref "C21") (pin "1") (pinfunction "1_1") (pintype "passive"))
      (node (ref "IC3") (pin "13") (pinfunction "-IN_13") (pintype "input"))
      (node (ref "R27") (pin "2") (pinfunction "2_2") (pintype "passive"))
      (node (ref "R28") (pin "2") (pinfunction "2_2") (pintype "passive"))
    )
    (net (code "44") (name "Net-(IC3D-OUT)") (class "Default")
      (node (ref "C21") (pin "2") (pinfunction "2_2") (pintype "passive"))
      (node (ref "IC3") (pin "14") (pinfunction "OUT_14") (pintype "output"))
      (node (ref "R18") (pin "1") (pinfunction "1_1") (pintype "passive"))
    )
    (net (code "45") (name "Net-(IC4-VI)") (class "Default")
      (node (ref "C25") (pin "1") (pinfunction "1_1") (pintype "passive"))
      (node (ref "IC4") (pin "1") (pinfunction "VI_1") (pintype "input"))
      (node (ref "SJ2") (pin "2") (pinfunction "2_2") (pintype "passive"))
    )
    (net (code "46") (name "Net-(IC4-VO)") (class "Default")
      (node (ref "C26") (pin "1") (pinfunction "1_1") (pintype "passive"))
      (node (ref "IC4") (pin "3") (pinfunction "VO_3") (pintype "passive"))
      (node (ref "L1") (pin "1") (pinfunction "1_1") (pintype "passive"))
    )
    (net (code "47") (name "Net-(IC5A-QA)") (class "Default")
      (node (ref "IC5") (pin "15") (pinfunction "QA_15") (pintype "tri_state"))
      (node (ref "R8") (pin "2") (pinfunction "2_2") (pintype "passive"))
    )
    (net (code "48") (name "Net-(IC5A-QB)") (class "Default")
      (node (ref "IC5") (pin "1") (pinfunction "QB_1") (pintype "tri_state"))
      (node (ref "R35") (pin "2") (pinfunction "2_2") (pintype "passive"))
    )
    (net (code "49") (name "Net-(IC5A-QC)") (class "Default")
      (node (ref "IC5") (pin "2") (pinfunction "QC_2") (pintype "tri_state"))
      (node (ref "R37") (pin "2") (pinfunction "2_2") (pintype "passive"))
    )
    (net (code "50") (name "Net-(IC5A-QD)") (class "Default")
      (node (ref "IC5") (pin "3") (pinfunction "QD_3") (pintype "tri_state"))
      (node (ref "R36") (pin "2") (pinfunction "2_2") (pintype "passive"))
    )
    (net (code "51") (name "Net-(IC5A-QE)") (class "Default")
      (node (ref "IC5") (pin "4") (pinfunction "QE_4") (pintype "tri_state"))
      (node (ref "R39") (pin "2") (pinfunction "2_2") (pintype "passive"))
    )
    (net (code "52") (name "Net-(IC5A-QF)") (class "Default")
      (node (ref "IC5") (pin "5") (pinfunction "QF_5") (pintype "tri_state"))
      (node (ref "R38") (pin "2") (pinfunction "2_2") (pintype "passive"))
    )
    (net (code "53") (name "Net-(IC5A-QG)") (class "Default")
      (node (ref "IC5") (pin "6") (pinfunction "QG_6") (pintype "tri_state"))
      (node (ref "R42") (pin "2") (pinfunction "2_2") (pintype "passive"))
    )
    (net (code "54") (name "Net-(IC5A-QH)") (class "Default")
      (node (ref "IC5") (pin "7") (pinfunction "QH_7") (pintype "tri_state"))
      (node (ref "R41") (pin "2") (pinfunction "2_2") (pintype "passive"))
    )
    (net (code "55") (name "Net-(J1F-MS)") (class "Default")
      (node (ref "D1") (pin "A") (pinfunction "A_A") (pintype "passive"))
      (node (ref "J1") (pin "A2") (pinfunction "MS_A2") (pintype "passive"))
    )
    (net (code "56") (name "Net-(J1N-MS)") (class "Default")
      (node (ref "J1") (pin "A4") (pinfunction "MS_A4") (pintype "passive"))
      (node (ref "SJ1") (pin "2") (pinfunction "2_2") (pintype "passive"))
    )
    (net (code "57") (name "Net-(L1-Pad2)") (class "Default")
      (node (ref "L1") (pin "2") (pinfunction "2_2") (pintype "passive"))
      (node (ref "SJ3") (pin "1") (pinfunction "1_1") (pintype "passive"))
    )
    (net (code "58") (name "Net-(LED1-PadA)") (class "Default")
      (node (ref "LED1") (pin "A") (pinfunction "A_A") (pintype "passive"))
      (node (ref "R8") (pin "1") (pinfunction "1_1") (pintype "passive"))
    )
    (net (code "59") (name "Net-(LED2A-A)") (class "Default")
      (node (ref "LED2") (pin "1A") (pinfunction "A_1A") (pintype "passive"))
      (node (ref "R39") (pin "1") (pinfunction "1_1") (pintype "passive"))
    )
    (net (code "60") (name "Net-(LED2B-A)") (class "Default")
      (node (ref "LED2") (pin "2A") (pinfunction "A_2A") (pintype "passive"))
      (node (ref "R38") (pin "1") (pinfunction "1_1") (pintype "passive"))
    )
    (net (code "61") (name "Net-(LED3A-A)") (class "Default")
      (node (ref "LED3") (pin "1A") (pinfunction "A_1A") (pintype "passive"))
      (node (ref "R42") (pin "1") (pinfunction "1_1") (pintype "passive"))
    )
    (net (code "62") (name "Net-(LED3B-A)") (class "Default")
      (node (ref "LED3") (pin "2A") (pinfunction "A_2A") (pintype "passive"))
      (node (ref "R41") (pin "1") (pinfunction "1_1") (pintype "passive"))
    )
    (net (code "63") (name "Net-(LED4-PadA)") (class "Default")
      (node (ref "LED4") (pin "A") (pinfunction "A_A") (pintype "passive"))
      (node (ref "R35") (pin "1") (pinfunction "1_1") (pintype "passive"))
    )
    (net (code "64") (name "Net-(LED6A-A)") (class "Default")
      (node (ref "LED6") (pin "1A") (pinfunction "A_1A") (pintype "passive"))
      (node (ref "R37") (pin "1") (pinfunction "1_1") (pintype "passive"))
    )
    (net (code "65") (name "Net-(LED6B-A)") (class "Default")
      (node (ref "LED6") (pin "2A") (pinfunction "A_2A") (pintype "passive"))
      (node (ref "R36") (pin "1") (pinfunction "1_1") (pintype "passive"))
    )
    (net (code "66") (name "Net-(Q2-B)") (class "Default")
      (node (ref "Q2") (pin "1") (pinfunction "B_1") (pintype "passive"))
      (node (ref "R18") (pin "2") (pinfunction "2_2") (pintype "passive"))
    )
    (net (code "67") (name "Net-(Q4-B)") (class "Default")
      (node (ref "Q4") (pin "1") (pinfunction "B_1") (pintype "passive"))
      (node (ref "R11") (pin "2") (pinfunction "2_2") (pintype "passive"))
    )
    (net (code "68") (name "Net-(R31-Pad2)") (class "Default")
      (node (ref "R31") (pin "2") (pinfunction "2_2") (pintype "passive"))
      (node (ref "T3") (pin "B") (pinfunction "B_B") (pintype "passive"))
    )
    (net (code "69") (name "Net-(R32-Pad2)") (class "Default")
      (node (ref "R32") (pin "2") (pinfunction "2_2") (pintype "passive"))
      (node (ref "T4") (pin "B") (pinfunction "B_B") (pintype "passive"))
    )
    (net (code "70") (name "RS_RX") (class "Default")
      (node (ref "IC1") (pin "1") (pinfunction "RO_1") (pintype "output"))
      (node (ref "IC2") (pin "30") (pinfunction "PD0(RXD)_30") (pintype "bidirectional"))
    )
    (net (code "71") (name "RS_TE") (class "Default")
      (node (ref "IC1") (pin "2") (pinfunction "RE/_2") (pintype "input"))
      (node (ref "IC1") (pin "3") (pinfunction "DE_3") (pintype "input"))
      (node (ref "IC2") (pin "32") (pinfunction "PD2(INT0)_32") (pintype "bidirectional"))
    )
    (net (code "72") (name "RS_TX") (class "Default")
      (node (ref "IC1") (pin "4") (pinfunction "DI_4") (pintype "input"))
      (node (ref "IC2") (pin "31") (pinfunction "PD1(TXD)_31") (pintype "bidirectional"))
    )
    (net (code "73") (name "SYS_SYNC") (class "Default")
      (node (ref "J1") (pin "C6") (pinfunction "MS_C6") (pintype "passive"))
    )
    (net (code "74") (name "SYS_USR_06") (class "Default")
      (node (ref "J1") (pin "A14") (pinfunction "MS_A14") (pintype "passive"))
    )
    (net (code "75") (name "SYS_USR_07") (class "Default")
      (node (ref "J1") (pin "C14") (pinfunction "MS_C14") (pintype "passive"))
    )
    (net (code "76") (name "SYS_USR_08") (class "Default")
      (node (ref "J1") (pin "A16") (pinfunction "MS_A16") (pintype "passive"))
    )
    (net (code "77") (name "SYS_USR_09") (class "Default")
      (node (ref "J1") (pin "C16") (pinfunction "MS_C16") (pintype "passive"))
    )
    (net (code "78") (name "SYS_USR_10") (class "Default")
      (node (ref "J1") (pin "A18") (pinfunction "MS_A18") (pintype "passive"))
    )
    (net (code "79") (name "SYS_USR_11") (class "Default")
      (node (ref "J1") (pin "C18") (pinfunction "MS_C18") (pintype "passive"))
    )
    (net (code "80") (name "SYS_USR_12") (class "Default")
      (node (ref "J1") (pin "A20") (pinfunction "MS_A20") (pintype "passive"))
    )
    (net (code "81") (name "SYS_USR_13") (class "Default")
      (node (ref "J1") (pin "C20") (pinfunction "MS_C20") (pintype "passive"))
    )
    (net (code "82") (name "SYS_USR_14") (class "Default")
      (node (ref "J1") (pin "A22") (pinfunction "MS_A22") (pintype "passive"))
    )
    (net (code "83") (name "SYS_USR_15") (class "Default")
      (node (ref "J1") (pin "C22") (pinfunction "MS_C22") (pintype "passive"))
    )
    (net (code "84") (name "SYS_USR_16") (class "Default")
      (node (ref "J1") (pin "A24") (pinfunction "MS_A24") (pintype "passive"))
    )
    (net (code "85") (name "SYS_USR_17") (class "Default")
      (node (ref "J1") (pin "C24") (pinfunction "MS_C24") (pintype "passive"))
    )
    (net (code "86") (name "SYS_USR_18") (class "Default")
      (node (ref "J1") (pin "A26") (pinfunction "MS_A26") (pintype "passive"))
    )
    (net (code "87") (name "SYS_USR_19") (class "Default")
      (node (ref "J1") (pin "C26") (pinfunction "MS_C26") (pintype "passive"))
    )
    (net (code "88") (name "SYS_USR_20") (class "Default")
      (node (ref "J1") (pin "A28") (pinfunction "MS_A28") (pintype "passive"))
    )
    (net (code "89") (name "SYS_USR_21") (class "Default")
      (node (ref "J1") (pin "C28") (pinfunction "MS_C28") (pintype "passive"))
    )
    (net (code "90") (name "ZAV_A") (class "Default")
      (node (ref "J1") (pin "A12") (pinfunction "MS_A12") (pintype "passive"))
      (node (ref "R40") (pin "1") (pinfunction "1_1") (pintype "passive"))
      (node (ref "T1") (pin "5") (pinfunction "D_5") (pintype "passive"))
      (node (ref "T1") (pin "6") (pinfunction "D1_6") (pintype "passive"))
      (node (ref "T1") (pin "7") (pinfunction "D_7") (pintype "passive"))
      (node (ref "T1") (pin "8") (pinfunction "D1_8") (pintype "passive"))
    )
    (net (code "91") (name "ZAV_B") (class "Default")
      (node (ref "J1") (pin "C12") (pinfunction "MS_C12") (pintype "passive"))
      (node (ref "R40") (pin "2") (pinfunction "2_2") (pintype "passive"))
      (node (ref "T2") (pin "5") (pinfunction "D_5") (pintype "passive"))
      (node (ref "T2") (pin "6") (pinfunction "D1_6") (pintype "passive"))
      (node (ref "T2") (pin "7") (pinfunction "D_7") (pintype "passive"))
      (node (ref "T2") (pin "8") (pinfunction "D1_8") (pintype "passive"))
    )
    (net (code "92") (name "unconnected-(IC2-ADC7-Pad22)") (class "Default")
      (node (ref "IC2") (pin "22") (pinfunction "ADC7_22") (pintype "bidirectional"))
    )
    (net (code "93") (name "unconnected-(IC2-PC0(ADC0)-Pad23)") (class "Default")
      (node (ref "IC2") (pin "23") (pinfunction "PC0(ADC0)_23") (pintype "bidirectional"))
    )
    (net (code "94") (name "unconnected-(IC2-PD4(XCK{slash}T0)-Pad2)") (class "Default")
      (node (ref "IC2") (pin "2") (pinfunction "PD4(XCK/T0)_2") (pintype "bidirectional"))
    )
    (net (code "95") (name "unconnected-(IC5A-QH*-Pad9)") (class "Default")
      (node (ref "IC5") (pin "9") (pinfunction "QH*_9") (pintype "tri_state"))
    )
    (net (code "96") (name "unconnected-(J1V-MS-PadC2)") (class "Default")
      (node (ref "J1") (pin "C2") (pinfunction "MS_C2") (pintype "passive"))
    )
    (net (code "97") (name "unconnected-(ZD1-NC-Pad2)") (class "Default")
      (node (ref "ZD1") (pin "2") (pinfunction "NC_2") (pintype "passive"))
    )
    (net (code "98") (name "unconnected-(ZD2-NC-Pad2)") (class "Default")
      (node (ref "ZD2") (pin "2") (pinfunction "NC_2") (pintype "passive"))
    )
    (net (code "99") (name "~{RST}") (class "Default")
      (node (ref "IC2") (pin "29") (pinfunction "PC6(/RESET)_29") (pintype "bidirectional"))
      (node (ref "R7") (pin "1") (pinfunction "1_1") (pintype "passive"))
      (node (ref "U1") (pin "4") (pinfunction "~{RST}_4") (pintype "input"))
    )
  )
)
